# QUTMS-TSAL-S03.net
KiCad netlist of a schematic drawn in Altium Designer
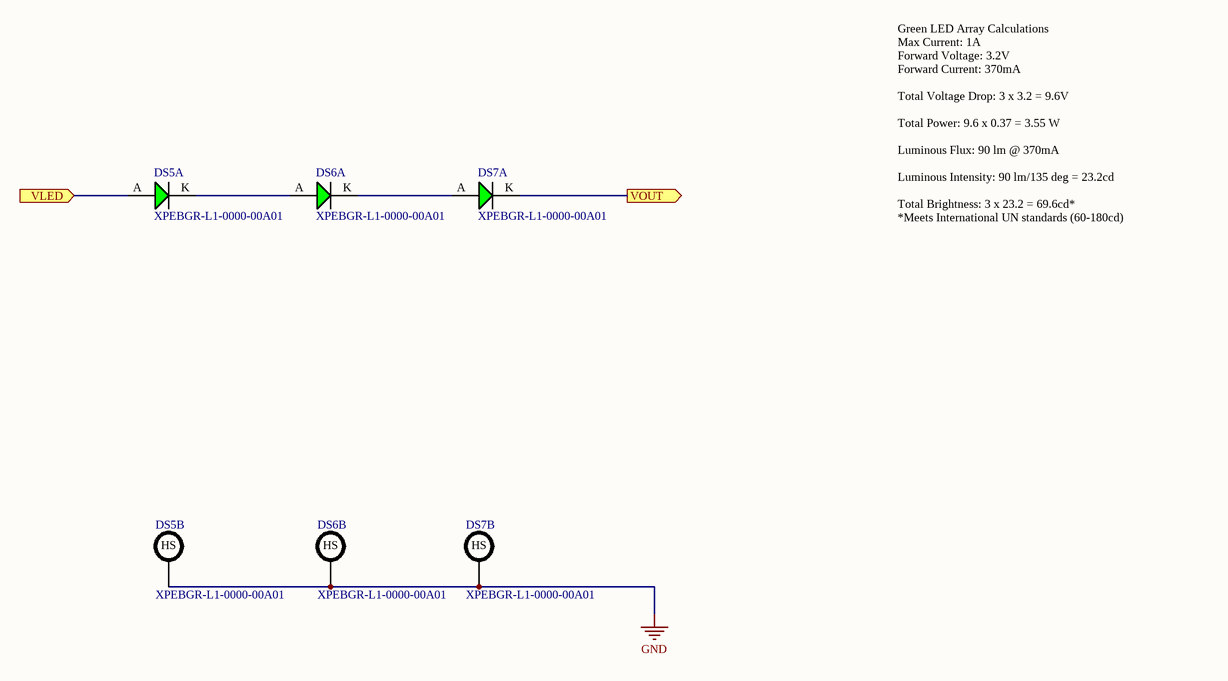
[diagram p0: QUTMS-TSAL-S03.SchDoc]

(export (version "E")
  (design (tool "Eeschema 10.0.6"))
  (components
    (comp (ref "DS5")
      (value "XPEBGR-L1-0000-00A01")
      (footprint "Cree XLamp XP-E2")
      (description "LED, Cree XLamp XP-E2 Series, Green, 535 nm, 135 °, 87.4 lm, 1 A")
      (libsource (lib "QUTMS_LEDLibrary") (part "XPEBGR-L1-0000-00A01"))
    )
    (comp (ref "DS6")
      (value "XPEBGR-L1-0000-00A01")
      (footprint "Cree XLamp XP-E2")
      (description "LED, Cree XLamp XP-E2 Series, Green, 535 nm, 135 °, 87.4 lm, 1 A")
      (libsource (lib "QUTMS_LEDLibrary") (part "XPEBGR-L1-0000-00A01"))
    )
    (comp (ref "DS7")
      (value "XPEBGR-L1-0000-00A01")
      (footprint "Cree XLamp XP-E2")
      (description "LED, Cree XLamp XP-E2 Series, Green, 535 nm, 135 °, 87.4 lm, 1 A")
      (libsource (lib "QUTMS_LEDLibrary") (part "XPEBGR-L1-0000-00A01"))
    )
  )
  (nets
    (net (code "1") (name "/VLED") (class "Default")
      (node (ref "DS5") (pin "A") (pinfunction "A_A") (pintype "passive"))
    )
    (net (code "2") (name "/VOUT") (class "Default")
      (node (ref "DS7") (pin "K") (pinfunction "K_K") (pintype "passive"))
    )
    (net (code "3") (name "GND") (class "Default")
      (node (ref "DS5") (pin "HS") (pinfunction "HS_HS") (pintype "passive"))
      (node (ref "DS6") (pin "HS") (pinfunction "HS_HS") (pintype "passive"))
      (node (ref "DS7") (pin "HS") (pinfunction "HS_HS") (pintype "passive"))
    )
    (net (code "4") (name "Net-(DS5-PadK)") (class "Default")
      (node (ref "DS5") (pin "K") (pinfunction "K_K") (pintype "passive"))
      (node (ref "DS6") (pin "A") (pinfunction "A_A") (pintype "passive"))
    )
    (net (code "5") (name "Net-(DS6-PadK)") (class "Default")
      (node (ref "DS6") (pin "K") (pinfunction "K_K") (pintype "passive"))
      (node (ref "DS7") (pin "A") (pinfunction "A_A") (pintype "passive"))
    )
  )
)
